# sidepcb11-03.net
KiCad netlist of a schematic drawn in EAGLE
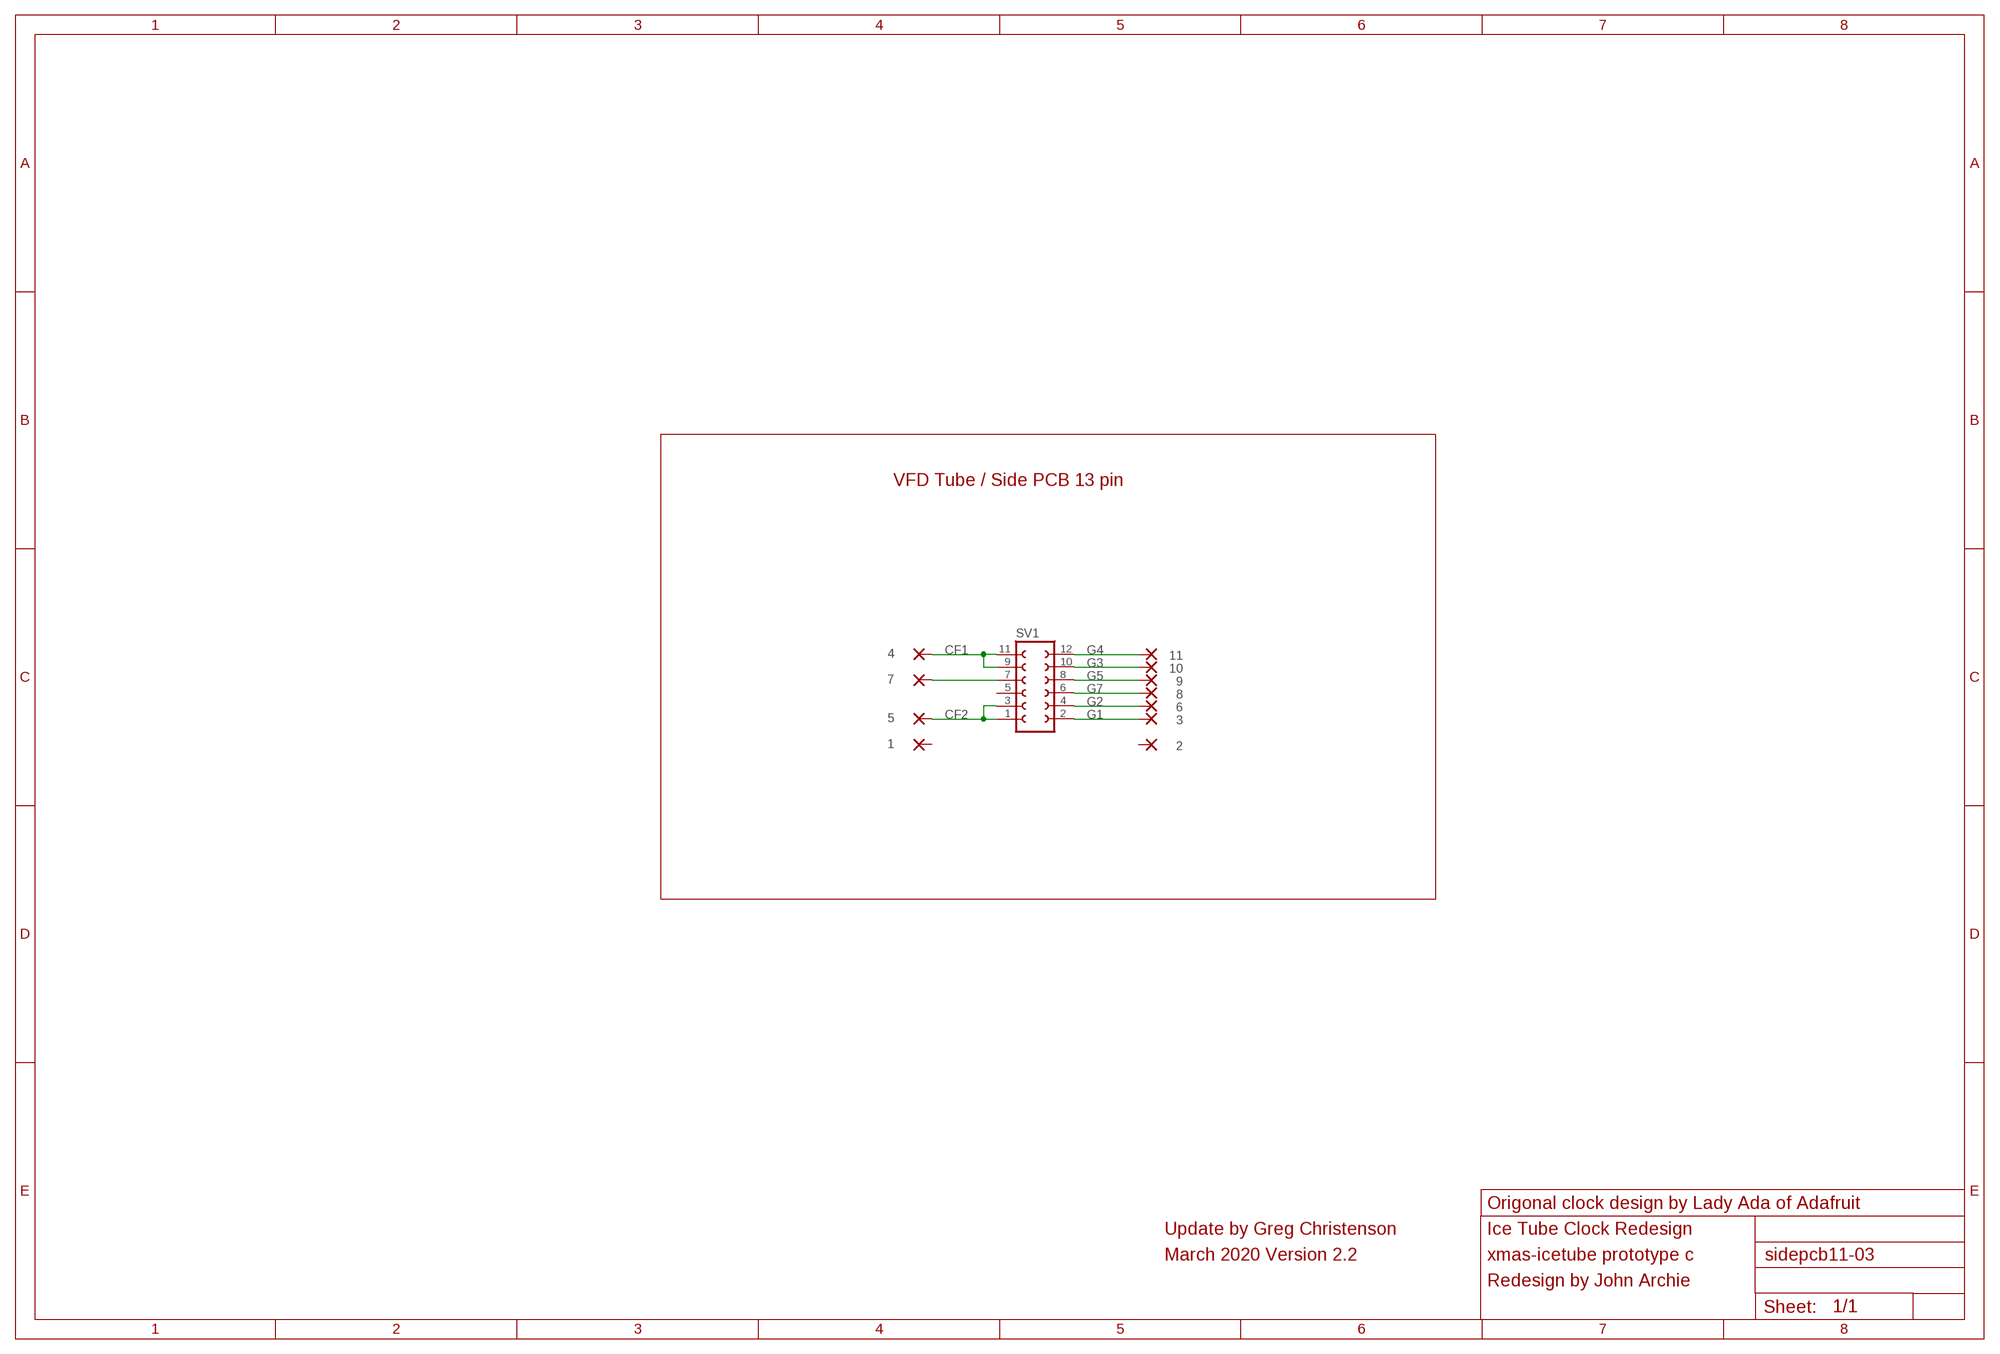
[diagram p0: schematic, sheet 1]

(export (version "E")
  (design (tool "Eeschema 10.0.6"))
  (components
    (comp (ref "1")
      (value "1,6/0,8")
      (footprint "eagle-import:1,6_0,8")
      (libsource (lib "eagle-import") (part "1,6/0,8"))
    )
    (comp (ref "2")
      (value "1,6/0,8")
      (footprint "eagle-import:1,6_0,8")
      (libsource (lib "eagle-import") (part "1,6/0,8"))
    )
    (comp (ref "3")
      (value "1,6/0,8")
      (footprint "eagle-import:1,6_0,8")
      (libsource (lib "eagle-import") (part "1,6/0,8"))
    )
    (comp (ref "4")
      (value "1,6/0,8")
      (footprint "eagle-import:1,6_0,8")
      (libsource (lib "eagle-import") (part "1,6/0,8"))
    )
    (comp (ref "5")
      (value "1,6/0,8")
      (footprint "eagle-import:1,6_0,8")
      (libsource (lib "eagle-import") (part "1,6/0,8"))
    )
    (comp (ref "6")
      (value "1,6/0,8")
      (footprint "eagle-import:1,6_0,8")
      (libsource (lib "eagle-import") (part "1,6/0,8"))
    )
    (comp (ref "7")
      (value "1,6/0,8")
      (footprint "eagle-import:1,6_0,8")
      (libsource (lib "eagle-import") (part "1,6/0,8"))
    )
    (comp (ref "8")
      (value "1,6/0,8")
      (footprint "eagle-import:1,6_0,8")
      (libsource (lib "eagle-import") (part "1,6/0,8"))
    )
    (comp (ref "9")
      (value "1,6/0,8")
      (footprint "eagle-import:1,6_0,8")
      (libsource (lib "eagle-import") (part "1,6/0,8"))
    )
    (comp (ref "10")
      (value "1,6/0,8")
      (footprint "eagle-import:1,6_0,8")
      (libsource (lib "eagle-import") (part "1,6/0,8"))
    )
    (comp (ref "11")
      (value "1,6/0,8")
      (footprint "eagle-import:1,6_0,8")
      (libsource (lib "eagle-import") (part "1,6/0,8"))
    )
    (comp (ref "SV1")
      (value "FE06-2W")
      (footprint "eagle-import:FE06-2W")
      (libsource (lib "eagle-import") (part "FE06-2W"))
    )
  )
  (nets
    (net (code "1") (name "/CF1") (class "Default")
      (node (ref "4") (pin "1") (pinfunction "P_1") (pintype "passive"))
      (node (ref "SV1") (pin "11") (pinfunction "11_11") (pintype "passive"))
      (node (ref "SV1") (pin "9") (pinfunction "9_9") (pintype "passive"))
    )
    (net (code "2") (name "/CF2") (class "Default")
      (node (ref "5") (pin "1") (pinfunction "P_1") (pintype "passive"))
      (node (ref "SV1") (pin "1") (pinfunction "1_1") (pintype "passive"))
      (node (ref "SV1") (pin "3") (pinfunction "3_3") (pintype "passive"))
    )
    (net (code "3") (name "/G1") (class "Default")
      (node (ref "3") (pin "1") (pinfunction "P_1") (pintype "passive"))
      (node (ref "SV1") (pin "2") (pinfunction "2_2") (pintype "passive"))
    )
    (net (code "4") (name "/G2") (class "Default")
      (node (ref "6") (pin "1") (pinfunction "P_1") (pintype "passive"))
      (node (ref "SV1") (pin "4") (pinfunction "4_4") (pintype "passive"))
    )
    (net (code "5") (name "/G3") (class "Default")
      (node (ref "10") (pin "1") (pinfunction "P_1") (pintype "passive"))
      (node (ref "SV1") (pin "10") (pinfunction "10_10") (pintype "passive"))
    )
    (net (code "6") (name "/G4") (class "Default")
      (node (ref "11") (pin "1") (pinfunction "P_1") (pintype "passive"))
      (node (ref "SV1") (pin "12") (pinfunction "12_12") (pintype "passive"))
    )
    (net (code "7") (name "/G5") (class "Default")
      (node (ref "9") (pin "1") (pinfunction "P_1") (pintype "passive"))
      (node (ref "SV1") (pin "8") (pinfunction "8_8") (pintype "passive"))
    )
    (net (code "8") (name "/G7") (class "Default")
      (node (ref "8") (pin "1") (pinfunction "P_1") (pintype "passive"))
      (node (ref "SV1") (pin "6") (pinfunction "6_6") (pintype "passive"))
    )
    (net (code "9") (name "Net-(7-P)") (class "Default")
      (node (ref "7") (pin "1") (pinfunction "P_1") (pintype "passive"))
      (node (ref "SV1") (pin "7") (pinfunction "7_7") (pintype "passive"))
    )
    (net (code "10") (name "unconnected-(1-P-Pad1)") (class "Default")
      (node (ref "1") (pin "1") (pinfunction "P_1") (pintype "passive"))
    )
    (net (code "11") (name "unconnected-(2-P-Pad1)") (class "Default")
      (node (ref "2") (pin "1") (pinfunction "P_1") (pintype "passive"))
    )
    (net (code "12") (name "unconnected-(SV1-Pad5)") (class "Default")
      (node (ref "SV1") (pin "5") (pinfunction "5_5") (pintype "passive"))
    )
  )
)
